# XSA.net
KiCad netlist of a schematic drawn in Altium Designer
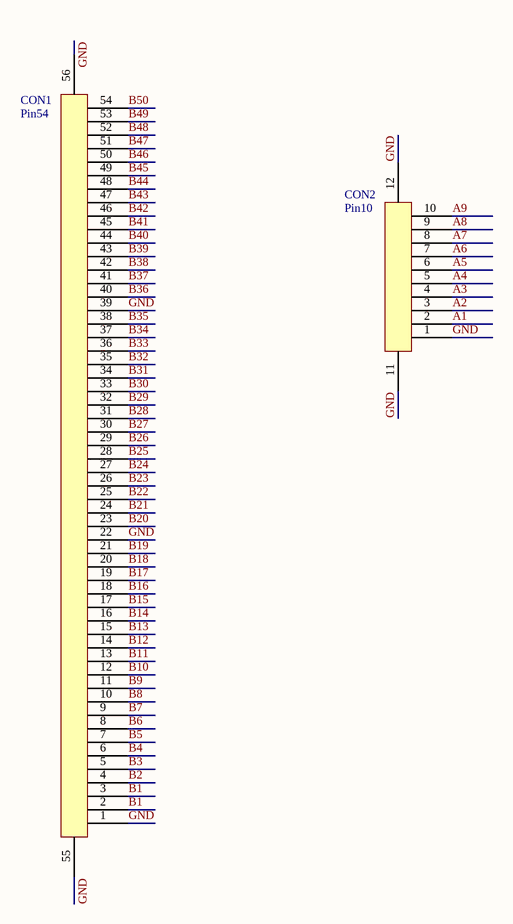
[diagram p0: XSA.SchDoc]

(export (version "E")
  (design (tool "Eeschema 10.0.6"))
  (components
    (comp (ref "CON1") (value "Pin54") (footprint "Pin54") (libsource (lib "IPHONEX") (part "Pin54")))
    (comp (ref "CON2") (value "Pin10") (footprint "Pin10") (libsource (lib "IPHONEX") (part "Pin10")))
  )
  (nets
    (net (code "1") (name "/A1") (class "Default") (node (ref "CON2") (pin "2") (pintype "passive")))
    (net (code "2") (name "/A2") (class "Default") (node (ref "CON2") (pin "3") (pintype "passive")))
    (net (code "3") (name "/A3") (class "Default") (node (ref "CON2") (pin "4") (pintype "passive")))
    (net (code "4") (name "/A4") (class "Default") (node (ref "CON2") (pin "5") (pintype "passive")))
    (net (code "5") (name "/A5") (class "Default") (node (ref "CON2") (pin "6") (pintype "passive")))
    (net (code "6") (name "/A6") (class "Default") (node (ref "CON2") (pin "7") (pintype "passive")))
    (net (code "7") (name "/A7") (class "Default") (node (ref "CON2") (pin "8") (pintype "passive")))
    (net (code "8") (name "/A8") (class "Default") (node (ref "CON2") (pin "9") (pintype "passive")))
    (net (code "9") (name "/A9") (class "Default") (node (ref "CON2") (pin "10") (pintype "passive")))
    (net (code "10") (name "/B1") (class "Default")
      (node (ref "CON1") (pin "2") (pintype "passive"))
      (node (ref "CON1") (pin "3") (pintype "passive"))
    )
    (net (code "11") (name "/B2") (class "Default") (node (ref "CON1") (pin "4") (pintype "passive")))
    (net (code "12") (name "/B3") (class "Default") (node (ref "CON1") (pin "5") (pintype "passive")))
    (net (code "13") (name "/B4") (class "Default") (node (ref "CON1") (pin "6") (pintype "passive")))
    (net (code "14") (name "/B5") (class "Default") (node (ref "CON1") (pin "7") (pintype "passive")))
    (net (code "15") (name "/B6") (class "Default") (node (ref "CON1") (pin "8") (pintype "passive")))
    (net (code "16") (name "/B7") (class "Default") (node (ref "CON1") (pin "9") (pintype "passive")))
    (net (code "17") (name "/B8") (class "Default") (node (ref "CON1") (pin "10") (pintype "passive")))
    (net (code "18") (name "/B9") (class "Default") (node (ref "CON1") (pin "11") (pintype "passive")))
    (net (code "19") (name "/B10") (class "Default") (node (ref "CON1") (pin "12") (pintype "passive")))
    (net (code "20") (name "/B11") (class "Default") (node (ref "CON1") (pin "13") (pintype "passive")))
    (net (code "21") (name "/B12") (class "Default") (node (ref "CON1") (pin "14") (pintype "passive")))
    (net (code "22") (name "/B13") (class "Default") (node (ref "CON1") (pin "15") (pintype "passive")))
    (net (code "23") (name "/B14") (class "Default") (node (ref "CON1") (pin "16") (pintype "passive")))
    (net (code "24") (name "/B15") (class "Default") (node (ref "CON1") (pin "17") (pintype "passive")))
    (net (code "25") (name "/B16") (class "Default") (node (ref "CON1") (pin "18") (pintype "passive")))
    (net (code "26") (name "/B17") (class "Default") (node (ref "CON1") (pin "19") (pintype "passive")))
    (net (code "27") (name "/B18") (class "Default") (node (ref "CON1") (pin "20") (pintype "passive")))
    (net (code "28") (name "/B19") (class "Default") (node (ref "CON1") (pin "21") (pintype "passive")))
    (net (code "29") (name "/B20") (class "Default") (node (ref "CON1") (pin "23") (pintype "passive")))
    (net (code "30") (name "/B21") (class "Default") (node (ref "CON1") (pin "24") (pintype "passive")))
    (net (code "31") (name "/B22") (class "Default") (node (ref "CON1") (pin "25") (pintype "passive")))
    (net (code "32") (name "/B23") (class "Default") (node (ref "CON1") (pin "26") (pintype "passive")))
    (net (code "33") (name "/B24") (class "Default") (node (ref "CON1") (pin "27") (pintype "passive")))
    (net (code "34") (name "/B25") (class "Default") (node (ref "CON1") (pin "28") (pintype "passive")))
    (net (code "35") (name "/B26") (class "Default") (node (ref "CON1") (pin "29") (pintype "passive")))
    (net (code "36") (name "/B27") (class "Default") (node (ref "CON1") (pin "30") (pintype "passive")))
    (net (code "37") (name "/B28") (class "Default") (node (ref "CON1") (pin "31") (pintype "passive")))
    (net (code "38") (name "/B29") (class "Default") (node (ref "CON1") (pin "32") (pintype "passive")))
    (net (code "39") (name "/B30") (class "Default") (node (ref "CON1") (pin "33") (pintype "passive")))
    (net (code "40") (name "/B31") (class "Default") (node (ref "CON1") (pin "34") (pintype "passive")))
    (net (code "41") (name "/B32") (class "Default") (node (ref "CON1") (pin "35") (pintype "passive")))
    (net (code "42") (name "/B33") (class "Default") (node (ref "CON1") (pin "36") (pintype "passive")))
    (net (code "43") (name "/B34") (class "Default") (node (ref "CON1") (pin "37") (pintype "passive")))
    (net (code "44") (name "/B35") (class "Default") (node (ref "CON1") (pin "38") (pintype "passive")))
    (net (code "45") (name "/B36") (class "Default") (node (ref "CON1") (pin "40") (pintype "passive")))
    (net (code "46") (name "/B37") (class "Default") (node (ref "CON1") (pin "41") (pintype "passive")))
    (net (code "47") (name "/B38") (class "Default") (node (ref "CON1") (pin "42") (pintype "passive")))
    (net (code "48") (name "/B39") (class "Default") (node (ref "CON1") (pin "43") (pintype "passive")))
    (net (code "49") (name "/B40") (class "Default") (node (ref "CON1") (pin "44") (pintype "passive")))
    (net (code "50") (name "/B41") (class "Default") (node (ref "CON1") (pin "45") (pintype "passive")))
    (net (code "51") (name "/B42") (class "Default") (node (ref "CON1") (pin "46") (pintype "passive")))
    (net (code "52") (name "/B43") (class "Default") (node (ref "CON1") (pin "47") (pintype "passive")))
    (net (code "53") (name "/B44") (class "Default") (node (ref "CON1") (pin "48") (pintype "passive")))
    (net (code "54") (name "/B45") (class "Default") (node (ref "CON1") (pin "49") (pintype "passive")))
    (net (code "55") (name "/B46") (class "Default") (node (ref "CON1") (pin "50") (pintype "passive")))
    (net (code "56") (name "/B47") (class "Default") (node (ref "CON1") (pin "51") (pintype "passive")))
    (net (code "57") (name "/B48") (class "Default") (node (ref "CON1") (pin "52") (pintype "passive")))
    (net (code "58") (name "/B49") (class "Default") (node (ref "CON1") (pin "53") (pintype "passive")))
    (net (code "59") (name "/B50") (class "Default") (node (ref "CON1") (pin "54") (pintype "passive")))
    (net (code "60") (name "/GND") (class "Default")
      (node (ref "CON1") (pin "1") (pintype "passive"))
      (node (ref "CON1") (pin "22") (pintype "passive"))
      (node (ref "CON1") (pin "39") (pintype "passive"))
      (node (ref "CON1") (pin "55") (pintype "passive"))
      (node (ref "CON1") (pin "56") (pintype "passive"))
      (node (ref "CON2") (pin "1") (pintype "passive"))
      (node (ref "CON2") (pin "11") (pintype "passive"))
      (node (ref "CON2") (pin "12") (pintype "passive"))
    )
  )
)
